# 4_RF_Attenuation_Amp.net
KiCad netlist of a schematic drawn in Altium Designer
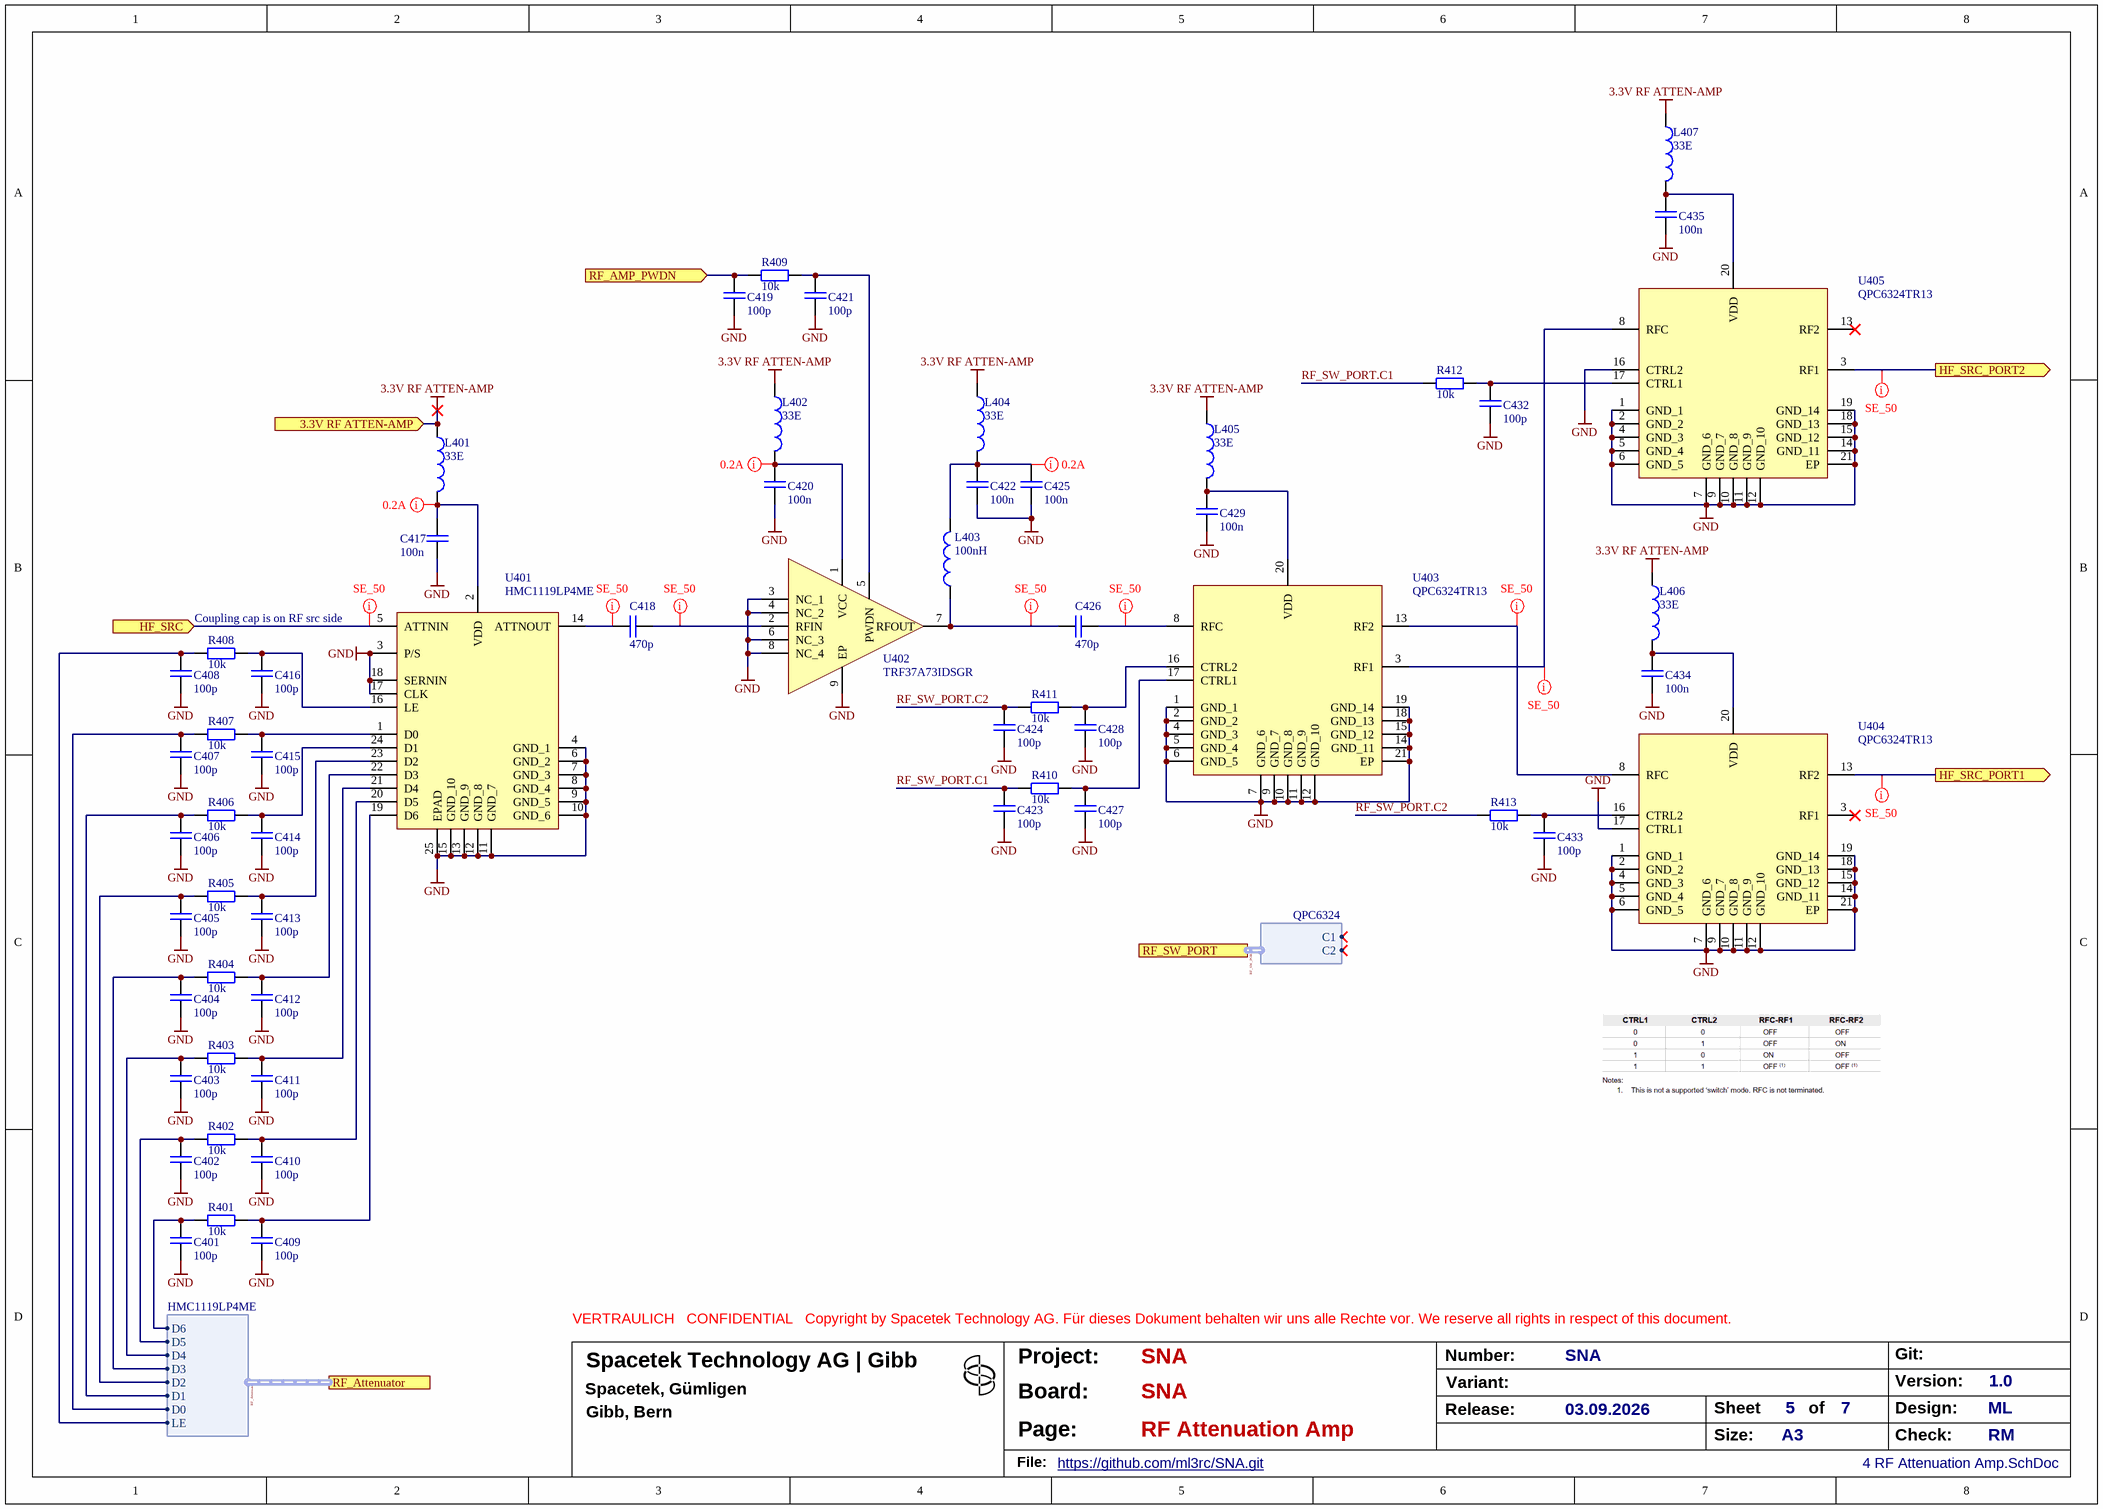
[diagram p0: 4 RF Attenuation Amp.SchDoc]

(export (version "E")
  (design (tool "Eeschema 10.0.6"))
  (components
    (comp (ref "C401")
      (value "100p")
      (footprint "STT--CC--0402")
      (description "Capacitor ceramic 100p 50V 5% C0G AEC-Q200 SMD--0402")
      (fields
        (field (name "PARTNUMBER") "CL05C101JB51PND")
        (field (name "MANUFACTURER") "Samsung Electro-Mechanics")
      )
      (libsource (lib "Spacetek Technology AG") (part "C--std"))
    )
    (comp (ref "C402")
      (value "100p")
      (footprint "STT--CC--0402")
      (description "Capacitor ceramic 100p 50V 5% C0G AEC-Q200 SMD--0402")
      (fields
        (field (name "PARTNUMBER") "CL05C101JB51PND")
        (field (name "MANUFACTURER") "Samsung Electro-Mechanics")
      )
      (libsource (lib "Spacetek Technology AG") (part "C--std"))
    )
    (comp (ref "C403")
      (value "100p")
      (footprint "STT--CC--0402")
      (description "Capacitor ceramic 100p 50V 5% C0G AEC-Q200 SMD--0402")
      (fields
        (field (name "PARTNUMBER") "CL05C101JB51PND")
        (field (name "MANUFACTURER") "Samsung Electro-Mechanics")
      )
      (libsource (lib "Spacetek Technology AG") (part "C--std"))
    )
    (comp (ref "C404")
      (value "100p")
      (footprint "STT--CC--0402")
      (description "Capacitor ceramic 100p 50V 5% C0G AEC-Q200 SMD--0402")
      (fields
        (field (name "PARTNUMBER") "CL05C101JB51PND")
        (field (name "MANUFACTURER") "Samsung Electro-Mechanics")
      )
      (libsource (lib "Spacetek Technology AG") (part "C--std"))
    )
    (comp (ref "C405")
      (value "100p")
      (footprint "STT--CC--0402")
      (description "Capacitor ceramic 100p 50V 5% C0G AEC-Q200 SMD--0402")
      (fields
        (field (name "PARTNUMBER") "CL05C101JB51PND")
        (field (name "MANUFACTURER") "Samsung Electro-Mechanics")
      )
      (libsource (lib "Spacetek Technology AG") (part "C--std"))
    )
    (comp (ref "C406")
      (value "100p")
      (footprint "STT--CC--0402")
      (description "Capacitor ceramic 100p 50V 5% C0G AEC-Q200 SMD--0402")
      (fields
        (field (name "PARTNUMBER") "CL05C101JB51PND")
        (field (name "MANUFACTURER") "Samsung Electro-Mechanics")
      )
      (libsource (lib "Spacetek Technology AG") (part "C--std"))
    )
    (comp (ref "C407")
      (value "100p")
      (footprint "STT--CC--0402")
      (description "Capacitor ceramic 100p 50V 5% C0G AEC-Q200 SMD--0402")
      (fields
        (field (name "PARTNUMBER") "CL05C101JB51PND")
        (field (name "MANUFACTURER") "Samsung Electro-Mechanics")
      )
      (libsource (lib "Spacetek Technology AG") (part "C--std"))
    )
    (comp (ref "C408")
      (value "100p")
      (footprint "STT--CC--0402")
      (description "Capacitor ceramic 100p 50V 5% C0G AEC-Q200 SMD--0402")
      (fields
        (field (name "PARTNUMBER") "CL05C101JB51PND")
        (field (name "MANUFACTURER") "Samsung Electro-Mechanics")
      )
      (libsource (lib "Spacetek Technology AG") (part "C--std"))
    )
    (comp (ref "C409")
      (value "100p")
      (footprint "STT--CC--0402")
      (description "Capacitor ceramic 100p 50V 5% C0G AEC-Q200 SMD--0402")
      (fields
        (field (name "PARTNUMBER") "CL05C101JB51PND")
        (field (name "MANUFACTURER") "Samsung Electro-Mechanics")
      )
      (libsource (lib "Spacetek Technology AG") (part "C--std"))
    )
    (comp (ref "C410")
      (value "100p")
      (footprint "STT--CC--0402")
      (description "Capacitor ceramic 100p 50V 5% C0G AEC-Q200 SMD--0402")
      (fields
        (field (name "PARTNUMBER") "CL05C101JB51PND")
        (field (name "MANUFACTURER") "Samsung Electro-Mechanics")
      )
      (libsource (lib "Spacetek Technology AG") (part "C--std"))
    )
    (comp (ref "C411")
      (value "100p")
      (footprint "STT--CC--0402")
      (description "Capacitor ceramic 100p 50V 5% C0G AEC-Q200 SMD--0402")
      (fields
        (field (name "PARTNUMBER") "CL05C101JB51PND")
        (field (name "MANUFACTURER") "Samsung Electro-Mechanics")
      )
      (libsource (lib "Spacetek Technology AG") (part "C--std"))
    )
    (comp (ref "C412")
      (value "100p")
      (footprint "STT--CC--0402")
      (description "Capacitor ceramic 100p 50V 5% C0G AEC-Q200 SMD--0402")
      (fields
        (field (name "PARTNUMBER") "CL05C101JB51PND")
        (field (name "MANUFACTURER") "Samsung Electro-Mechanics")
      )
      (libsource (lib "Spacetek Technology AG") (part "C--std"))
    )
    (comp (ref "C413")
      (value "100p")
      (footprint "STT--CC--0402")
      (description "Capacitor ceramic 100p 50V 5% C0G AEC-Q200 SMD--0402")
      (fields
        (field (name "PARTNUMBER") "CL05C101JB51PND")
        (field (name "MANUFACTURER") "Samsung Electro-Mechanics")
      )
      (libsource (lib "Spacetek Technology AG") (part "C--std"))
    )
    (comp (ref "C414")
      (value "100p")
      (footprint "STT--CC--0402")
      (description "Capacitor ceramic 100p 50V 5% C0G AEC-Q200 SMD--0402")
      (fields
        (field (name "PARTNUMBER") "CL05C101JB51PND")
        (field (name "MANUFACTURER") "Samsung Electro-Mechanics")
      )
      (libsource (lib "Spacetek Technology AG") (part "C--std"))
    )
    (comp (ref "C415")
      (value "100p")
      (footprint "STT--CC--0402")
      (description "Capacitor ceramic 100p 50V 5% C0G AEC-Q200 SMD--0402")
      (fields
        (field (name "PARTNUMBER") "CL05C101JB51PND")
        (field (name "MANUFACTURER") "Samsung Electro-Mechanics")
      )
      (libsource (lib "Spacetek Technology AG") (part "C--std"))
    )
    (comp (ref "C416")
      (value "100p")
      (footprint "STT--CC--0402")
      (description "Capacitor ceramic 100p 50V 5% C0G AEC-Q200 SMD--0402")
      (fields
        (field (name "PARTNUMBER") "CL05C101JB51PND")
        (field (name "MANUFACTURER") "Samsung Electro-Mechanics")
      )
      (libsource (lib "Spacetek Technology AG") (part "C--std"))
    )
    (comp (ref "C417")
      (value "100n")
      (footprint "STT--CC--0402")
      (description "Capacitor ceramic 100n 16V 10% X7R  SMD--0402")
      (fields (field (name "VOLTAGE") "16V") (field (name "TOLERANCE") "10%"))
      (libsource (lib "Spacetek Technology AG") (part "C--std"))
    )
    (comp (ref "C418")
      (value "470p")
      (footprint "STT--CC--0402")
      (description "Capacitor ceramic 470p 50V 5% C0G  SMD--0402")
      (fields (field (name "MANUFACTURER") "TDK") (field (name "PARTNUMBER") "CGA2B2C0G1H471J050BA"))
      (libsource (lib "Spacetek Technology AG") (part "C--std"))
    )
    (comp (ref "C419")
      (value "100p")
      (footprint "STT--CC--0402")
      (description "Capacitor ceramic 100p 50V 5% C0G AEC-Q200 SMD--0402")
      (fields
        (field (name "PARTNUMBER") "CL05C101JB51PND")
        (field (name "MANUFACTURER") "Samsung Electro-Mechanics")
      )
      (libsource (lib "Spacetek Technology AG") (part "C--std"))
    )
    (comp (ref "C420")
      (value "100n")
      (footprint "STT--CC--0402")
      (description "Capacitor ceramic 100n 16V 10% X7R  SMD--0402")
      (fields (field (name "VOLTAGE") "16V") (field (name "TOLERANCE") "10%"))
      (libsource (lib "Spacetek Technology AG") (part "C--std"))
    )
    (comp (ref "C421")
      (value "100p")
      (footprint "STT--CC--0402")
      (description "Capacitor ceramic 100p 50V 5% C0G AEC-Q200 SMD--0402")
      (fields
        (field (name "PARTNUMBER") "CL05C101JB51PND")
        (field (name "MANUFACTURER") "Samsung Electro-Mechanics")
      )
      (libsource (lib "Spacetek Technology AG") (part "C--std"))
    )
    (comp (ref "C422")
      (value "100n")
      (footprint "STT--CC--0402")
      (description "Capacitor ceramic 100n 16V 10% X7R  SMD--0402")
      (fields (field (name "VOLTAGE") "16V") (field (name "TOLERANCE") "10%"))
      (libsource (lib "Spacetek Technology AG") (part "C--std"))
    )
    (comp (ref "C423")
      (value "100p")
      (footprint "STT--CC--0402")
      (description "Capacitor ceramic 100p 50V 5% C0G AEC-Q200 SMD--0402")
      (fields
        (field (name "PARTNUMBER") "CL05C101JB51PND")
        (field (name "MANUFACTURER") "Samsung Electro-Mechanics")
      )
      (libsource (lib "Spacetek Technology AG") (part "C--std"))
    )
    (comp (ref "C424")
      (value "100p")
      (footprint "STT--CC--0402")
      (description "Capacitor ceramic 100p 50V 5% C0G AEC-Q200 SMD--0402")
      (fields
        (field (name "PARTNUMBER") "CL05C101JB51PND")
        (field (name "MANUFACTURER") "Samsung Electro-Mechanics")
      )
      (libsource (lib "Spacetek Technology AG") (part "C--std"))
    )
    (comp (ref "C425")
      (value "100n")
      (footprint "STT--CC--0402")
      (description "Capacitor ceramic 100n 16V 10% X7R  SMD--0402")
      (fields (field (name "VOLTAGE") "16V") (field (name "TOLERANCE") "10%"))
      (libsource (lib "Spacetek Technology AG") (part "C--std"))
    )
    (comp (ref "C426")
      (value "470p")
      (footprint "STT--CC--0402")
      (description "Capacitor ceramic 470p 50V 5% C0G  SMD--0402")
      (fields (field (name "MANUFACTURER") "TDK") (field (name "PARTNUMBER") "CGA2B2C0G1H471J050BA"))
      (libsource (lib "Spacetek Technology AG") (part "C--std"))
    )
    (comp (ref "C427")
      (value "100p")
      (footprint "STT--CC--0402")
      (description "Capacitor ceramic 100p 50V 5% C0G AEC-Q200 SMD--0402")
      (fields
        (field (name "PARTNUMBER") "CL05C101JB51PND")
        (field (name "MANUFACTURER") "Samsung Electro-Mechanics")
      )
      (libsource (lib "Spacetek Technology AG") (part "C--std"))
    )
    (comp (ref "C428")
      (value "100p")
      (footprint "STT--CC--0402")
      (description "Capacitor ceramic 100p 50V 5% C0G AEC-Q200 SMD--0402")
      (fields
        (field (name "PARTNUMBER") "CL05C101JB51PND")
        (field (name "MANUFACTURER") "Samsung Electro-Mechanics")
      )
      (libsource (lib "Spacetek Technology AG") (part "C--std"))
    )
    (comp (ref "C429")
      (value "100n")
      (footprint "STT--CC--0402")
      (description "Capacitor ceramic 100n 16V 10% X7R  SMD--0402")
      (fields (field (name "VOLTAGE") "16V") (field (name "TOLERANCE") "10%"))
      (libsource (lib "Spacetek Technology AG") (part "C--std"))
    )
    (comp (ref "C432")
      (value "100p")
      (footprint "STT--CC--0402")
      (description "Capacitor ceramic 100p 50V 5% C0G AEC-Q200 SMD--0402")
      (fields
        (field (name "PARTNUMBER") "CL05C101JB51PND")
        (field (name "MANUFACTURER") "Samsung Electro-Mechanics")
      )
      (libsource (lib "Spacetek Technology AG") (part "C--std"))
    )
    (comp (ref "C433")
      (value "100p")
      (footprint "STT--CC--0402")
      (description "Capacitor ceramic 100p 50V 5% C0G AEC-Q200 SMD--0402")
      (fields
        (field (name "PARTNUMBER") "CL05C101JB51PND")
        (field (name "MANUFACTURER") "Samsung Electro-Mechanics")
      )
      (libsource (lib "Spacetek Technology AG") (part "C--std"))
    )
    (comp (ref "C434")
      (value "100n")
      (footprint "STT--CC--0402")
      (description "Capacitor ceramic 100n 16V 10% X7R  SMD--0402")
      (fields (field (name "VOLTAGE") "16V") (field (name "TOLERANCE") "10%"))
      (libsource (lib "Spacetek Technology AG") (part "C--std"))
    )
    (comp (ref "C435")
      (value "100n")
      (footprint "STT--CC--0402")
      (description "Capacitor ceramic 100n 16V 10% X7R  SMD--0402")
      (fields (field (name "VOLTAGE") "16V") (field (name "TOLERANCE") "10%"))
      (libsource (lib "Spacetek Technology AG") (part "C--std"))
    )
    (comp (ref "L401")
      (value "33E")
      (footprint "STT--FB--0402")
      (description "Ferrit Bead MPZ1005S330HT000 33E 3A 22mE SMD--0402")
      (fields (field (name "MANUFACTURER") "TDK Group") (field (name "PARTNUMBER") "MPZ1005S330HT000"))
      (libsource (lib "Spacetek Technology AG") (part "L--std"))
    )
    (comp (ref "L402")
      (value "33E")
      (footprint "STT--FB--0402")
      (description "Ferrit Bead MPZ1005S330HT000 33E 3A 22mE SMD--0402")
      (fields (field (name "MANUFACTURER") "TDK Group") (field (name "PARTNUMBER") "MPZ1005S330HT000"))
      (libsource (lib "Spacetek Technology AG") (part "L--std"))
    )
    (comp (ref "L403")
      (value "100nH")
      (footprint "STT--RC--0603")
      (description "Inductor 100nH 290mA AEC-Q200  SMD--0603")
      (fields (field (name "MANUFACTURER") "Coilcraft") (field (name "PARTNUMBER") "0603DC-R10XJRW"))
      (libsource (lib "Spacetek Technology AG") (part "L--std"))
    )
    (comp (ref "L404")
      (value "33E")
      (footprint "STT--FB--0402")
      (description "Ferrit Bead MPZ1005S330HT000 33E 3A 22mE SMD--0402")
      (fields (field (name "MANUFACTURER") "TDK Group") (field (name "PARTNUMBER") "MPZ1005S330HT000"))
      (libsource (lib "Spacetek Technology AG") (part "L--std"))
    )
    (comp (ref "L405")
      (value "33E")
      (footprint "STT--FB--0402")
      (description "Ferrit Bead MPZ1005S330HT000 33E 3A 22mE SMD--0402")
      (fields (field (name "MANUFACTURER") "TDK Group") (field (name "PARTNUMBER") "MPZ1005S330HT000"))
      (libsource (lib "Spacetek Technology AG") (part "L--std"))
    )
    (comp (ref "L406")
      (value "33E")
      (footprint "STT--FB--0402")
      (description "Ferrit Bead MPZ1005S330HT000 33E 3A 22mE SMD--0402")
      (fields (field (name "MANUFACTURER") "TDK Group") (field (name "PARTNUMBER") "MPZ1005S330HT000"))
      (libsource (lib "Spacetek Technology AG") (part "L--std"))
    )
    (comp (ref "L407")
      (value "33E")
      (footprint "STT--FB--0402")
      (description "Ferrit Bead MPZ1005S330HT000 33E 3A 22mE SMD--0402")
      (fields (field (name "MANUFACTURER") "TDK Group") (field (name "PARTNUMBER") "MPZ1005S330HT000"))
      (libsource (lib "Spacetek Technology AG") (part "L--std"))
    )
    (comp (ref "R401")
      (value "10k")
      (footprint "STT--RC--0402")
      (description "Resistor 10k 50V  0.063W 1%  SMD--0402")
      (fields (field (name "PARTNUMBER") "ERJ-2RKF1002X") (field (name "MANUFACTURER") "Panasonic"))
      (libsource (lib "Spacetek Technology AG") (part "R--std"))
    )
    (comp (ref "R402")
      (value "10k")
      (footprint "STT--RC--0402")
      (description "Resistor 10k 50V  0.063W 1%  SMD--0402")
      (fields (field (name "PARTNUMBER") "ERJ-2RKF1002X") (field (name "MANUFACTURER") "Panasonic"))
      (libsource (lib "Spacetek Technology AG") (part "R--std"))
    )
    (comp (ref "R403")
      (value "10k")
      (footprint "STT--RC--0402")
      (description "Resistor 10k 50V  0.063W 1%  SMD--0402")
      (fields (field (name "PARTNUMBER") "ERJ-2RKF1002X") (field (name "MANUFACTURER") "Panasonic"))
      (libsource (lib "Spacetek Technology AG") (part "R--std"))
    )
    (comp (ref "R404")
      (value "10k")
      (footprint "STT--RC--0402")
      (description "Resistor 10k 50V  0.063W 1%  SMD--0402")
      (fields (field (name "PARTNUMBER") "ERJ-2RKF1002X") (field (name "MANUFACTURER") "Panasonic"))
      (libsource (lib "Spacetek Technology AG") (part "R--std"))
    )
    (comp (ref "R405")
      (value "10k")
      (footprint "STT--RC--0402")
      (description "Resistor 10k 50V  0.063W 1%  SMD--0402")
      (fields (field (name "PARTNUMBER") "ERJ-2RKF1002X") (field (name "MANUFACTURER") "Panasonic"))
      (libsource (lib "Spacetek Technology AG") (part "R--std"))
    )
    (comp (ref "R406")
      (value "10k")
      (footprint "STT--RC--0402")
      (description "Resistor 10k 50V  0.063W 1%  SMD--0402")
      (fields (field (name "PARTNUMBER") "ERJ-2RKF1002X") (field (name "MANUFACTURER") "Panasonic"))
      (libsource (lib "Spacetek Technology AG") (part "R--std"))
    )
    (comp (ref "R407")
      (value "10k")
      (footprint "STT--RC--0402")
      (description "Resistor 10k 50V  0.063W 1%  SMD--0402")
      (fields (field (name "PARTNUMBER") "ERJ-2RKF1002X") (field (name "MANUFACTURER") "Panasonic"))
      (libsource (lib "Spacetek Technology AG") (part "R--std"))
    )
    (comp (ref "R408")
      (value "10k")
      (footprint "STT--RC--0402")
      (description "Resistor 10k 50V  0.063W 1%  SMD--0402")
      (fields (field (name "PARTNUMBER") "ERJ-2RKF1002X") (field (name "MANUFACTURER") "Panasonic"))
      (libsource (lib "Spacetek Technology AG") (part "R--std"))
    )
    (comp (ref "R409")
      (value "10k")
      (footprint "STT--RC--0402")
      (description "Resistor 10k 50V  0.063W 1%  SMD--0402")
      (fields (field (name "PARTNUMBER") "ERJ-2RKF1002X") (field (name "MANUFACTURER") "Panasonic"))
      (libsource (lib "") (part "R--std_1"))
    )
    (comp (ref "R410")
      (value "10k")
      (footprint "STT--RC--0402")
      (description "Resistor 10k 50V  0.063W 1%  SMD--0402")
      (fields (field (name "PARTNUMBER") "ERJ-2RKF1002X") (field (name "MANUFACTURER") "Panasonic"))
      (libsource (lib "Spacetek Technology AG") (part "R--std"))
    )
    (comp (ref "R411")
      (value "10k")
      (footprint "STT--RC--0402")
      (description "Resistor 10k 50V  0.063W 1%  SMD--0402")
      (fields (field (name "PARTNUMBER") "ERJ-2RKF1002X") (field (name "MANUFACTURER") "Panasonic"))
      (libsource (lib "Spacetek Technology AG") (part "R--std"))
    )
    (comp (ref "R412")
      (value "10k")
      (footprint "STT--RC--0402")
      (description "Resistor 10k 50V  0.063W 1%  SMD--0402")
      (fields (field (name "PARTNUMBER") "ERJ-2RKF1002X") (field (name "MANUFACTURER") "Panasonic"))
      (libsource (lib "Spacetek Technology AG") (part "R--std"))
    )
    (comp (ref "R413")
      (value "10k")
      (footprint "STT--RC--0402")
      (description "Resistor 10k 50V  0.063W 1%  SMD--0402")
      (fields (field (name "PARTNUMBER") "ERJ-2RKF1002X") (field (name "MANUFACTURER") "Panasonic"))
      (libsource (lib "Spacetek Technology AG") (part "R--std"))
    )
    (comp (ref "U401")
      (value "HMC1119LP4ME")
      (footprint "ADI--IC--LFCSP-24")
      (description "Attenuator HMC1119LP4ME, -2...-32dBm, 0.1-6Ghz")
      (fields (field (name "MANUFACTURER") "Analog Devices"))
      (libsource (lib "Spacetek Technology AG") (part "ADI--HMC1119LP4ME"))
    )
    (comp (ref "U402")
      (value "TRF37A73IDSGR")
      (footprint "TI--IC--WSON-8")
      (description "Amp TRF37A73IDSGR, +12dB, 0.1-6Ghz")
      (fields (field (name "MANUFACTURER") "Texas Instruments"))
      (libsource (lib "Spacetek Technology AG") (part "TI--TRF37A73IDSGR"))
    )
    (comp (ref "U403")
      (value "QPC6324TR13")
      (footprint "QV--IC--QFN-20")
      (description "RF Switch QPC6324TR13  5-6000MHz SPDT")
      (fields (field (name "MANUFACTURER") "Qorvo"))
      (libsource (lib "Spacetek Technology AG") (part "QV-QPC6324TR13"))
    )
    (comp (ref "U404")
      (value "QPC6324TR13")
      (footprint "QV--IC--QFN-20")
      (description "RF Switch QPC6324TR13  5-6000MHz SPDT")
      (fields (field (name "MANUFACTURER") "Qorvo"))
      (libsource (lib "Spacetek Technology AG") (part "QV-QPC6324TR13"))
    )
    (comp (ref "U405")
      (value "QPC6324TR13")
      (footprint "QV--IC--QFN-20")
      (description "RF Switch QPC6324TR13  5-6000MHz SPDT")
      (fields (field (name "MANUFACTURER") "Qorvo"))
      (libsource (lib "Spacetek Technology AG") (part "QV-QPC6324TR13"))
    )
  )
  (nets
    (net (code "3") (name "/HF_SRC") (class "Default")
      (node (ref "U401") (pin "5") (pinfunction "ATTNIN_5") (pintype "passive"))
    )
    (net (code "4") (name "/HF_SRC_PORT1") (class "Default")
      (node (ref "U404") (pin "13") (pinfunction "RF2_13") (pintype "passive"))
    )
    (net (code "5") (name "/HF_SRC_PORT2") (class "Default")
      (node (ref "U405") (pin "3") (pinfunction "RF1_3") (pintype "passive"))
    )
    (net (code "6") (name "/RF_AMP_PWDN") (class "Default")
      (node (ref "C419") (pin "2") (pinfunction "2_2") (pintype "passive"))
      (node (ref "R409") (pin "1") (pinfunction "1_1") (pintype "passive"))
    )
    (net (code "8") (name "/RF_SW_PORT.C1") (class "Default")
      (node (ref "C423") (pin "2") (pinfunction "2_2") (pintype "passive"))
      (node (ref "R410") (pin "2") (pinfunction "2_2") (pintype "passive"))
      (node (ref "R412") (pin "2") (pinfunction "2_2") (pintype "passive"))
    )
    (net (code "9") (name "/RF_SW_PORT.C2") (class "Default")
      (node (ref "C424") (pin "2") (pinfunction "2_2") (pintype "passive"))
      (node (ref "R411") (pin "2") (pinfunction "2_2") (pintype "passive"))
      (node (ref "R413") (pin "2") (pinfunction "2_2") (pintype "passive"))
    )
    (net (code "11") (name "3.3V RF ATTEN-AMP") (class "Default")
      (node (ref "L401") (pin "1") (pinfunction "1_1") (pintype "passive"))
      (node (ref "L402") (pin "1") (pinfunction "1_1") (pintype "passive"))
      (node (ref "L404") (pin "1") (pinfunction "1_1") (pintype "passive"))
      (node (ref "L405") (pin "1") (pinfunction "1_1") (pintype "passive"))
      (node (ref "L406") (pin "1") (pinfunction "1_1") (pintype "passive"))
      (node (ref "L407") (pin "1") (pinfunction "1_1") (pintype "passive"))
    )
    (net (code "12") (name "GND") (class "Default")
      (node (ref "C401") (pin "1") (pinfunction "1_1") (pintype "passive"))
      (node (ref "C402") (pin "1") (pinfunction "1_1") (pintype "passive"))
      (node (ref "C403") (pin "1") (pinfunction "1_1") (pintype "passive"))
      (node (ref "C404") (pin "1") (pinfunction "1_1") (pintype "passive"))
      (node (ref "C405") (pin "1") (pinfunction "1_1") (pintype "passive"))
      (node (ref "C406") (pin "1") (pinfunction "1_1") (pintype "passive"))
      (node (ref "C407") (pin "1") (pinfunction "1_1") (pintype "passive"))
      (node (ref "C408") (pin "1") (pinfunction "1_1") (pintype "passive"))
      (node (ref "C409") (pin "1") (pinfunction "1_1") (pintype "passive"))
      (node (ref "C410") (pin "1") (pinfunction "1_1") (pintype "passive"))
      (node (ref "C411") (pin "1") (pinfunction "1_1") (pintype "passive"))
      (node (ref "C412") (pin "1") (pinfunction "1_1") (pintype "passive"))
      (node (ref "C413") (pin "1") (pinfunction "1_1") (pintype "passive"))
      (node (ref "C414") (pin "1") (pinfunction "1_1") (pintype "passive"))
      (node (ref "C415") (pin "1") (pinfunction "1_1") (pintype "passive"))
      (node (ref "C416") (pin "1") (pinfunction "1_1") (pintype "passive"))
      (node (ref "C417") (pin "2") (pinfunction "2_2") (pintype "passive"))
      (node (ref "C419") (pin "1") (pinfunction "1_1") (pintype "passive"))
      (node (ref "C420") (pin "1") (pinfunction "1_1") (pintype "passive"))
      (node (ref "C421") (pin "1") (pinfunction "1_1") (pintype "passive"))
      (node (ref "C422") (pin "1") (pinfunction "1_1") (pintype "passive"))
      (node (ref "C423") (pin "1") (pinfunction "1_1") (pintype "passive"))
      (node (ref "C424") (pin "1") (pinfunction "1_1") (pintype "passive"))
      (node (ref "C425") (pin "1") (pinfunction "1_1") (pintype "passive"))
      (node (ref "C427") (pin "1") (pinfunction "1_1") (pintype "passive"))
      (node (ref "C428") (pin "1") (pinfunction "1_1") (pintype "passive"))
      (node (ref "C429") (pin "1") (pinfunction "1_1") (pintype "passive"))
      (node (ref "C432") (pin "1") (pinfunction "1_1") (pintype "passive"))
      (node (ref "C433") (pin "1") (pinfunction "1_1") (pintype "passive"))
      (node (ref "C434") (pin "1") (pinfunction "1_1") (pintype "passive"))
      (node (ref "C435") (pin "1") (pinfunction "1_1") (pintype "passive"))
      (node (ref "U401") (pin "10") (pinfunction "GND_6_10") (pintype "passive"))
      (node (ref "U401") (pin "11") (pinfunction "GND_7_11") (pintype "passive"))
      (node (ref "U401") (pin "12") (pinfunction "GND_8_12") (pintype "passive"))
      (node (ref "U401") (pin "13") (pinfunction "GND_9_13") (pintype "passive"))
      (node (ref "U401") (pin "15") (pinfunction "GND_10_15") (pintype "passive"))
      (node (ref "U401") (pin "17") (pinfunction "CLK_17") (pintype "passive"))
      (node (ref "U401") (pin "18") (pinfunction "SERNIN_18") (pintype "passive"))
      (node (ref "U401") (pin "25") (pinfunction "EPAD_25") (pintype "passive"))
      (node (ref "U401") (pin "3") (pinfunction "P/S_3") (pintype "passive"))
      (node (ref "U401") (pin "4") (pinfunction "GND_1_4") (pintype "passive"))
      (node (ref "U401") (pin "6") (pinfunction "GND_2_6") (pintype "passive"))
      (node (ref "U401") (pin "7") (pinfunction "GND_3_7") (pintype "passive"))
      (node (ref "U401") (pin "8") (pinfunction "GND_4_8") (pintype "passive"))
      (node (ref "U401") (pin "9") (pinfunction "GND_5_9") (pintype "passive"))
      (node (ref "U402") (pin "3") (pinfunction "NC_1_3") (pintype "passive"))
      (node (ref "U402") (pin "4") (pinfunction "NC_2_4") (pintype "passive"))
      (node (ref "U402") (pin "6") (pinfunction "NC_3_6") (pintype "passive"))
      (node (ref "U402") (pin "8") (pinfunction "NC_4_8") (pintype "passive"))
      (node (ref "U402") (pin "9") (pinfunction "EP_9") (pintype "passive"))
      (node (ref "U403") (pin "1") (pinfunction "GND_1_1") (pintype "passive"))
      (node (ref "U403") (pin "10") (pinfunction "GND_8_10") (pintype "passive"))
      (node (ref "U403") (pin "11") (pinfunction "GND_9_11") (pintype "passive"))
      (node (ref "U403") (pin "12") (pinfunction "GND_10_12") (pintype "passive"))
      (node (ref "U403") (pin "14") (pinfunction "GND_11_14") (pintype "passive"))
      (node (ref "U403") (pin "15") (pinfunction "GND_12_15") (pintype "passive"))
      (node (ref "U403") (pin "18") (pinfunction "GND_13_18") (pintype "passive"))
      (node (ref "U403") (pin "19") (pinfunction "GND_14_19") (pintype "passive"))
      (node (ref "U403") (pin "2") (pinfunction "GND_2_2") (pintype "passive"))
      (node (ref "U403") (pin "21") (pinfunction "EP_21") (pintype "passive"))
      (node (ref "U403") (pin "4") (pinfunction "GND_3_4") (pintype "passive"))
      (node (ref "U403") (pin "5") (pinfunction "GND_4_5") (pintype "passive"))
      (node (ref "U403") (pin "6") (pinfunction "GND_5_6") (pintype "passive"))
      (node (ref "U403") (pin "7") (pinfunction "GND_6_7") (pintype "passive"))
      (node (ref "U403") (pin "9") (pinfunction "GND_7_9") (pintype "passive"))
      (node (ref "U404") (pin "1") (pinfunction "GND_1_1") (pintype "passive"))
      (node (ref "U404") (pin "10") (pinfunction "GND_8_10") (pintype "passive"))
      (node (ref "U404") (pin "11") (pinfunction "GND_9_11") (pintype "passive"))
      (node (ref "U404") (pin "12") (pinfunction "GND_10_12") (pintype "passive"))
      (node (ref "U404") (pin "14") (pinfunction "GND_11_14") (pintype "passive"))
      (node (ref "U404") (pin "15") (pinfunction "GND_12_15") (pintype "passive"))
      (node (ref "U404") (pin "17") (pinfunction "CTRL1_17") (pintype "passive"))
      (node (ref "U404") (pin "18") (pinfunction "GND_13_18") (pintype "passive"))
      (node (ref "U404") (pin "19") (pinfunction "GND_14_19") (pintype "passive"))
      (node (ref "U404") (pin "2") (pinfunction "GND_2_2") (pintype "passive"))
      (node (ref "U404") (pin "21") (pinfunction "EP_21") (pintype "passive"))
      (node (ref "U404") (pin "4") (pinfunction "GND_3_4") (pintype "passive"))
      (node (ref "U404") (pin "5") (pinfunction "GND_4_5") (pintype "passive"))
      (node (ref "U404") (pin "6") (pinfunction "GND_5_6") (pintype "passive"))
      (node (ref "U404") (pin "7") (pinfunction "GND_6_7") (pintype "passive"))
      (node (ref "U404") (pin "9") (pinfunction "GND_7_9") (pintype "passive"))
      (node (ref "U405") (pin "1") (pinfunction "GND_1_1") (pintype "passive"))
      (node (ref "U405") (pin "10") (pinfunction "GND_8_10") (pintype "passive"))
      (node (ref "U405") (pin "11") (pinfunction "GND_9_11") (pintype "passive"))
      (node (ref "U405") (pin "12") (pinfunction "GND_10_12") (pintype "passive"))
      (node (ref "U405") (pin "14") (pinfunction "GND_11_14") (pintype "passive"))
      (node (ref "U405") (pin "15") (pinfunction "GND_12_15") (pintype "passive"))
      (node (ref "U405") (pin "16") (pinfunction "CTRL2_16") (pintype "passive"))
      (node (ref "U405") (pin "18") (pinfunction "GND_13_18") (pintype "passive"))
      (node (ref "U405") (pin "19") (pinfunction "GND_14_19") (pintype "passive"))
      (node (ref "U405") (pin "2") (pinfunction "GND_2_2") (pintype "passive"))
      (node (ref "U405") (pin "21") (pinfunction "EP_21") (pintype "passive"))
      (node (ref "U405") (pin "4") (pinfunction "GND_3_4") (pintype "passive"))
      (node (ref "U405") (pin "5") (pinfunction "GND_4_5") (pintype "passive"))
      (node (ref "U405") (pin "6") (pinfunction "GND_5_6") (pintype "passive"))
      (node (ref "U405") (pin "7") (pinfunction "GND_6_7") (pintype "passive"))
      (node (ref "U405") (pin "9") (pinfunction "GND_7_9") (pintype "passive"))
    )
    (net (code "13") (name "Net-(C401-Pad2)") (class "Default")
      (node (ref "C401") (pin "2") (pinfunction "2_2") (pintype "passive"))
      (node (ref "R401") (pin "2") (pinfunction "2_2") (pintype "passive"))
    )
    (net (code "14") (name "Net-(C402-Pad2)") (class "Default")
      (node (ref "C402") (pin "2") (pinfunction "2_2") (pintype "passive"))
      (node (ref "R402") (pin "2") (pinfunction "2_2") (pintype "passive"))
    )
    (net (code "15") (name "Net-(C403-Pad2)") (class "Default")
      (node (ref "C403") (pin "2") (pinfunction "2_2") (pintype "passive"))
      (node (ref "R403") (pin "2") (pinfunction "2_2") (pintype "passive"))
    )
    (net (code "16") (name "Net-(C404-Pad2)") (class "Default")
      (node (ref "C404") (pin "2") (pinfunction "2_2") (pintype "passive"))
      (node (ref "R404") (pin "2") (pinfunction "2_2") (pintype "passive"))
    )
    (net (code "17") (name "Net-(C405-Pad2)") (class "Default")
      (node (ref "C405") (pin "2") (pinfunction "2_2") (pintype "passive"))
      (node (ref "R405") (pin "2") (pinfunction "2_2") (pintype "passive"))
    )
    (net (code "18") (name "Net-(C406-Pad2)") (class "Default")
      (node (ref "C406") (pin "2") (pinfunction "2_2") (pintype "passive"))
      (node (ref "R406") (pin "2") (pinfunction "2_2") (pintype "passive"))
    )
    (net (code "19") (name "Net-(C407-Pad2)") (class "Default")
      (node (ref "C407") (pin "2") (pinfunction "2_2") (pintype "passive"))
      (node (ref "R407") (pin "2") (pinfunction "2_2") (pintype "passive"))
    )
    (net (code "20") (name "Net-(C408-Pad2)") (class "Default")
      (node (ref "C408") (pin "2") (pinfunction "2_2") (pintype "passive"))
      (node (ref "R408") (pin "2") (pinfunction "2_2") (pintype "passive"))
    )
    (net (code "21") (name "Net-(C422-Pad2)") (class "Default")
      (node (ref "C422") (pin "2") (pinfunction "2_2") (pintype "passive"))
      (node (ref "C425") (pin "2") (pinfunction "2_2") (pintype "passive"))
      (node (ref "L403") (pin "2") (pinfunction "2_2") (pintype "passive"))
      (node (ref "L404") (pin "2") (pinfunction "2_2") (pintype "passive"))
    )
    (net (code "22") (name "Net-(U401-ATTNOUT)") (class "Default")
      (node (ref "C418") (pin "1") (pinfunction "1_1") (pintype "passive"))
      (node (ref "U401") (pin "14") (pinfunction "ATTNOUT_14") (pintype "passive"))
    )
    (net (code "23") (name "Net-(U401-D0)") (class "Default")
      (node (ref "C415") (pin "2") (pinfunction "2_2") (pintype "passive"))
      (node (ref "R407") (pin "1") (pinfunction "1_1") (pintype "passive"))
      (node (ref "U401") (pin "1") (pinfunction "D0_1") (pintype "passive"))
    )
    (net (code "24") (name "Net-(U401-D1)") (class "Default")
      (node (ref "C414") (pin "2") (pinfunction "2_2") (pintype "passive"))
      (node (ref "R406") (pin "1") (pinfunction "1_1") (pintype "passive"))
      (node (ref "U401") (pin "24") (pinfunction "D1_24") (pintype "passive"))
    )
    (net (code "25") (name "Net-(U401-D2)") (class "Default")
      (node (ref "C413") (pin "2") (pinfunction "2_2") (pintype "passive"))
      (node (ref "R405") (pin "1") (pinfunction "1_1") (pintype "passive"))
      (node (ref "U401") (pin "23") (pinfunction "D2_23") (pintype "passive"))
    )
    (net (code "26") (name "Net-(U401-D3)") (class "Default")
      (node (ref "C412") (pin "2") (pinfunction "2_2") (pintype "passive"))
      (node (ref "R404") (pin "1") (pinfunction "1_1") (pintype "passive"))
      (node (ref "U401") (pin "22") (pinfunction "D3_22") (pintype "passive"))
    )
    (net (code "27") (name "Net-(U401-D4)") (class "Default")
      (node (ref "C411") (pin "2") (pinfunction "2_2") (pintype "passive"))
      (node (ref "R403") (pin "1") (pinfunction "1_1") (pintype "passive"))
      (node (ref "U401") (pin "21") (pinfunction "D4_21") (pintype "passive"))
    )
    (net (code "28") (name "Net-(U401-D5)") (class "Default")
      (node (ref "C410") (pin "2") (pinfunction "2_2") (pintype "passive"))
      (node (ref "R402") (pin "1") (pinfunction "1_1") (pintype "passive"))
      (node (ref "U401") (pin "20") (pinfunction "D5_20") (pintype "passive"))
    )
    (net (code "29") (name "Net-(U401-D6)") (class "Default")
      (node (ref "C409") (pin "2") (pinfunction "2_2") (pintype "passive"))
      (node (ref "R401") (pin "1") (pinfunction "1_1") (pintype "passive"))
      (node (ref "U401") (pin "19") (pinfunction "D6_19") (pintype "passive"))
    )
    (net (code "30") (name "Net-(U401-LE)") (class "Default")
      (node (ref "C416") (pin "2") (pinfunction "2_2") (pintype "passive"))
      (node (ref "R408") (pin "1") (pinfunction "1_1") (pintype "passive"))
      (node (ref "U401") (pin "16") (pinfunction "LE_16") (pintype "passive"))
    )
    (net (code "31") (name "Net-(U401-VDD)") (class "Default")
      (node (ref "C417") (pin "1") (pinfunction "1_1") (pintype "passive"))
      (node (ref "L401") (pin "2") (pinfunction "2_2") (pintype "passive"))
      (node (ref "U401") (pin "2") (pinfunction "VDD_2") (pintype "passive"))
    )
    (net (code "32") (name "Net-(U402-PWDN)") (class "Default")
      (node (ref "C421") (pin "2") (pinfunction "2_2") (pintype "passive"))
      (node (ref "R409") (pin "2") (pinfunction "2_2") (pintype "passive"))
      (node (ref "U402") (pin "5") (pinfunction "PWDN_5") (pintype "passive"))
    )
    (net (code "33") (name "Net-(U402-RFIN)") (class "Default")
      (node (ref "C418") (pin "2") (pinfunction "2_2") (pintype "passive"))
      (node (ref "U402") (pin "2") (pinfunction "RFIN_2") (pintype "passive"))
    )
    (net (code "34") (name "Net-(U402-RFOUT)") (class "Default")
      (node (ref "C426") (pin "1") (pinfunction "1_1") (pintype "passive"))
      (node (ref "L403") (pin "1") (pinfunction "1_1") (pintype "passive"))
      (node (ref "U402") (pin "7") (pinfunction "RFOUT_7") (pintype "passive"))
    )
    (net (code "35") (name "Net-(U402-VCC)") (class "Default")
      (node (ref "C420") (pin "2") (pinfunction "2_2") (pintype "passive"))
      (node (ref "L402") (pin "2") (pinfunction "2_2") (pintype "passive"))
      (node (ref "U402") (pin "1") (pinfunction "VCC_1") (pintype "passive"))
    )
    (net (code "36") (name "Net-(U403-CTRL1)") (class "Default")
      (node (ref "C427") (pin "2") (pinfunction "2_2") (pintype "passive"))
      (node (ref "R410") (pin "1") (pinfunction "1_1") (pintype "passive"))
      (node (ref "U403") (pin "17") (pinfunction "CTRL1_17") (pintype "passive"))
    )
    (net (code "37") (name "Net-(U403-CTRL2)") (class "Default")
      (node (ref "C428") (pin "2") (pinfunction "2_2") (pintype "passive"))
      (node (ref "R411") (pin "1") (pinfunction "1_1") (pintype "passive"))
      (node (ref "U403") (pin "16") (pinfunction "CTRL2_16") (pintype "passive"))
    )
    (net (code "38") (name "Net-(U403-RF1)") (class "Default")
      (node (ref "U403") (pin "3") (pinfunction "RF1_3") (pintype "passive"))
      (node (ref "U405") (pin "8") (pinfunction "RFC_8") (pintype "passive"))
    )
    (net (code "39") (name "Net-(U403-RF2)") (class "Default")
      (node (ref "U403") (pin "13") (pinfunction "RF2_13") (pintype "passive"))
      (node (ref "U404") (pin "8") (pinfunction "RFC_8") (pintype "passive"))
    )
    (net (code "40") (name "Net-(U403-RFC)") (class "Default")
      (node (ref "C426") (pin "2") (pinfunction "2_2") (pintype "passive"))
      (node (ref "U403") (pin "8") (pinfunction "RFC_8") (pintype "passive"))
    )
    (net (code "41") (name "Net-(U403-VDD)") (class "Default")
      (node (ref "C429") (pin "2") (pinfunction "2_2") (pintype "passive"))
      (node (ref "L405") (pin "2") (pinfunction "2_2") (pintype "passive"))
      (node (ref "U403") (pin "20") (pinfunction "VDD_20") (pintype "passive"))
    )
    (net (code "42") (name "Net-(U404-CTRL2)") (class "Default")
      (node (ref "C433") (pin "2") (pinfunction "2_2") (pintype "passive"))
      (node (ref "R413") (pin "1") (pinfunction "1_1") (pintype "passive"))
      (node (ref "U404") (pin "16") (pinfunction "CTRL2_16") (pintype "passive"))
    )
    (net (code "43") (name "Net-(U404-VDD)") (class "Default")
      (node (ref "C434") (pin "2") (pinfunction "2_2") (pintype "passive"))
      (node (ref "L406") (pin "2") (pinfunction "2_2") (pintype "passive"))
      (node (ref "U404") (pin "20") (pinfunction "VDD_20") (pintype "passive"))
    )
    (net (code "44") (name "Net-(U405-CTRL1)") (class "Default")
      (node (ref "C432") (pin "2") (pinfunction "2_2") (pintype "passive"))
      (node (ref "R412") (pin "1") (pinfunction "1_1") (pintype "passive"))
      (node (ref "U405") (pin "17") (pinfunction "CTRL1_17") (pintype "passive"))
    )
    (net (code "45") (name "Net-(U405-VDD)") (class "Default")
      (node (ref "C435") (pin "2") (pinfunction "2_2") (pintype "passive"))
      (node (ref "L407") (pin "2") (pinfunction "2_2") (pintype "passive"))
      (node (ref "U405") (pin "20") (pinfunction "VDD_20") (pintype "passive"))
    )
    (net (code "46") (name "unconnected-(U404-RF1-Pad3)") (class "Default")
      (node (ref "U404") (pin "3") (pinfunction "RF1_3") (pintype "passive+no_connect"))
    )
    (net (code "47") (name "unconnected-(U405-RF2-Pad13)") (class "Default")
      (node (ref "U405") (pin "13") (pinfunction "RF2_13") (pintype "passive+no_connect"))
    )
  )
)
